# ElectroChemCC_PWM.net
KiCad netlist of a schematic drawn in EAGLE
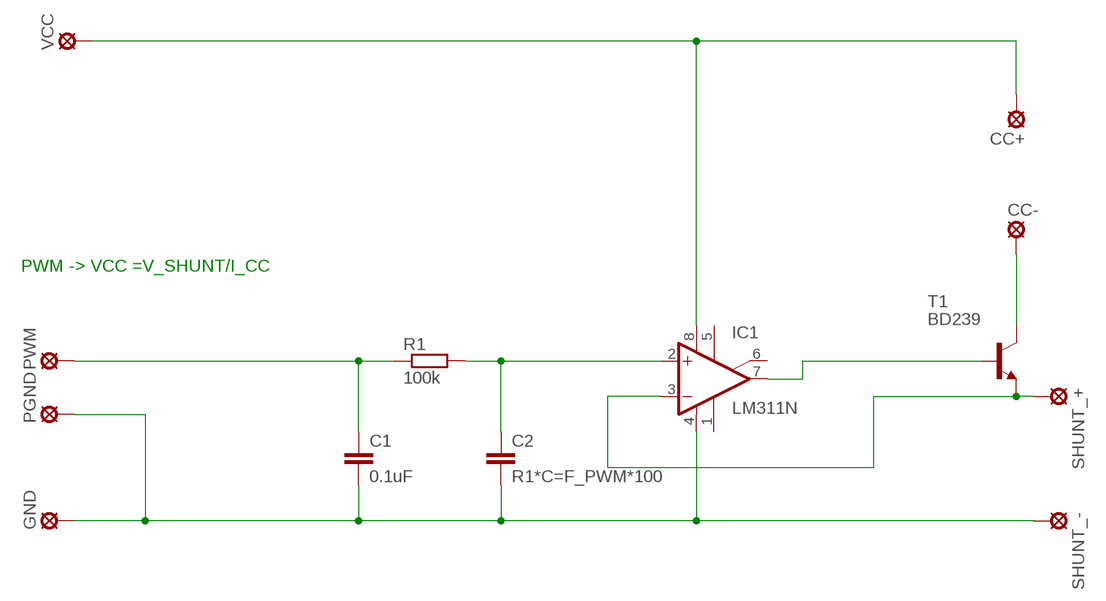
[diagram p0: schematic, sheet 1]

(export (version "E")
  (design (tool "Eeschema 10.0.6"))
  (components
    (comp (ref "C1")
      (value "0.1uF")
      (footprint "eagle-import:C050-025X075")
      (libsource (lib "eagle-import") (part "C-EU050-025X075"))
    )
    (comp (ref "C2")
      (value "R1*C=F_PWM*100")
      (footprint "eagle-import:C050-025X075")
      (libsource (lib "eagle-import") (part "C-EU050-025X075"))
    )
    (comp (ref "CC+")
      (value "LSP10")
      (footprint "eagle-import:LSP10")
      (libsource (lib "eagle-import") (part "LSP10"))
    )
    (comp (ref "CC-")
      (value "LSP10")
      (footprint "eagle-import:LSP10")
      (libsource (lib "eagle-import") (part "LSP10"))
    )
    (comp (ref "GND")
      (value "LSP10")
      (footprint "eagle-import:LSP10")
      (libsource (lib "eagle-import") (part "LSP10"))
    )
    (comp (ref "IC1")
      (value "LM311N")
      (footprint "eagle-import:DIL08")
      (libsource (lib "eagle-import") (part "LM311N"))
    )
    (comp (ref "PGND")
      (value "LSP10")
      (footprint "eagle-import:LSP10")
      (libsource (lib "eagle-import") (part "LSP10"))
    )
    (comp (ref "PWM")
      (value "LSP10")
      (footprint "eagle-import:LSP10")
      (libsource (lib "eagle-import") (part "LSP10"))
    )
    (comp (ref "R1")
      (value "100k")
      (footprint "eagle-import:0207_10")
      (libsource (lib "eagle-import") (part "R-EU_0207/10"))
    )
    (comp (ref "SHUNT_+")
      (value "LSP10")
      (footprint "eagle-import:LSP10")
      (libsource (lib "eagle-import") (part "LSP10"))
    )
    (comp (ref "SHUNT_-")
      (value "LSP10")
      (footprint "eagle-import:LSP10")
      (libsource (lib "eagle-import") (part "LSP10"))
    )
    (comp (ref "T1")
      (value "BD239")
      (footprint "eagle-import:TO220")
      (libsource (lib "eagle-import") (part "BD239"))
    )
    (comp (ref "VCC")
      (value "LSP10")
      (footprint "eagle-import:LSP10")
      (libsource (lib "eagle-import") (part "LSP10"))
    )
  )
  (nets
    (net (code "1") (name "Net-(C1-Pad1)") (class "Default")
      (node (ref "C1") (pin "1") (pinfunction "1_1") (pintype "passive"))
      (node (ref "PWM") (pin "MP") (pinfunction "MP_MP") (pintype "passive"))
      (node (ref "R1") (pin "1") (pinfunction "1_1") (pintype "passive"))
    )
    (net (code "2") (name "Net-(IC1-+IN)") (class "Default")
      (node (ref "C2") (pin "1") (pinfunction "1_1") (pintype "passive"))
      (node (ref "IC1") (pin "2") (pinfunction "+IN_2") (pintype "input"))
      (node (ref "R1") (pin "2") (pinfunction "2_2") (pintype "passive"))
    )
    (net (code "3") (name "Net-(IC1--IN)") (class "Default")
      (node (ref "IC1") (pin "3") (pinfunction "-IN_3") (pintype "input"))
      (node (ref "SHUNT_+") (pin "MP") (pinfunction "MP_MP") (pintype "passive"))
      (node (ref "T1") (pin "3") (pinfunction "E_3") (pintype "passive"))
    )
    (net (code "4") (name "Net-(IC1-OUT)") (class "Default")
      (node (ref "IC1") (pin "7") (pinfunction "OUT_7") (pintype "output"))
      (node (ref "T1") (pin "1") (pinfunction "B_1") (pintype "passive"))
    )
    (net (code "5") (name "Net-(IC1-V+)") (class "Default")
      (node (ref "CC+") (pin "MP") (pinfunction "MP_MP") (pintype "passive"))
      (node (ref "IC1") (pin "8") (pinfunction "V+_8") (pintype "power_in"))
      (node (ref "VCC") (pin "MP") (pinfunction "MP_MP") (pintype "passive"))
    )
    (net (code "6") (name "Net-(IC1-V-)") (class "Default")
      (node (ref "C1") (pin "2") (pinfunction "2_2") (pintype "passive"))
      (node (ref "C2") (pin "2") (pinfunction "2_2") (pintype "passive"))
      (node (ref "GND") (pin "MP") (pinfunction "MP_MP") (pintype "passive"))
      (node (ref "IC1") (pin "4") (pinfunction "V-_4") (pintype "power_in"))
      (node (ref "PGND") (pin "MP") (pinfunction "MP_MP") (pintype "passive"))
      (node (ref "SHUNT_-") (pin "MP") (pinfunction "MP_MP") (pintype "passive"))
    )
    (net (code "7") (name "Net-(T1-C)") (class "Default")
      (node (ref "CC-") (pin "MP") (pinfunction "MP_MP") (pintype "passive"))
      (node (ref "T1") (pin "2") (pinfunction "C_2") (pintype "passive"))
    )
    (net (code "8") (name "unconnected-(IC1-GND-Pad1)") (class "Default")
      (node (ref "IC1") (pin "1") (pinfunction "GND_1") (pintype "passive"))
    )
    (net (code "9") (name "unconnected-(IC1-ON-Pad5)") (class "Default")
      (node (ref "IC1") (pin "5") (pinfunction "ON_5") (pintype "passive"))
    )
    (net (code "10") (name "unconnected-(IC1-ON{slash}STR-Pad6)") (class "Default")
      (node (ref "IC1") (pin "6") (pinfunction "ON/STR_6") (pintype "passive"))
    )
  )
)
